# USB.net
KiCad netlist of a schematic drawn in Altium Designer
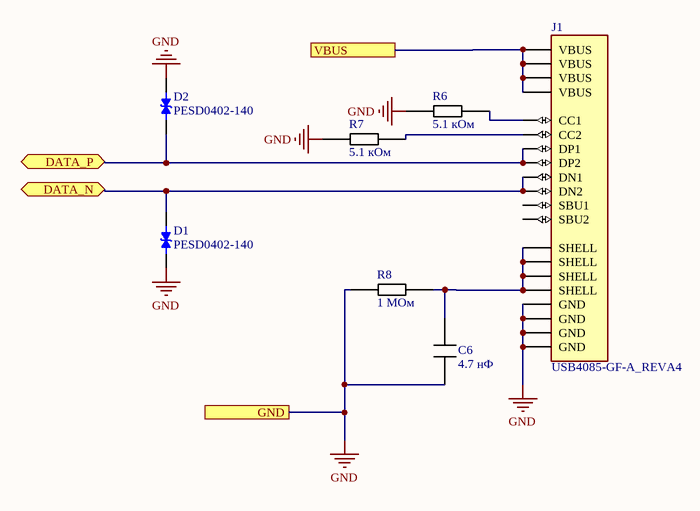
[diagram p0: USB.SchDoc]

(export (version "E")
  (design (tool "Eeschema 10.0.6"))
  (components
    (comp (ref "C6")
      (value "4.7 нФ")
      (footprint "WURTH 885012206012")
      (libsource (lib "Schlib1") (part "WURTH 885012206012"))
    )
    (comp (ref "D1")
      (value "PESD0402-140")
      (footprint "DIO_PESD0402-140")
      (description "40V Clamp - Ipp Tvs Diode Surface Mount 0402")
      (fields (field (name "MF") "Littelfuse Inc."))
      (libsource (lib "PESD0402-140") (part "PESD0402-140"))
    )
    (comp (ref "D2")
      (value "PESD0402-140")
      (footprint "DIO_PESD0402-140")
      (description "40V Clamp - Ipp Tvs Diode Surface Mount 0402")
      (fields (field (name "MF") "Littelfuse Inc."))
      (libsource (lib "PESD0402-140") (part "PESD0402-140"))
    )
    (comp (ref "J1")
      (value "USB4085-GF-A_REVA4")
      (footprint "GCT_USB4085-GF-A_REVA4")
      (fields (field (name "MP") "USB4085-GF-A") (field (name "MF") "Global Connector Technology"))
      (libsource (lib "USB4085-GF-A_REVA4") (part "USB4085-GF-A_REVA4"))
    )
    (comp (ref "R6")
      (value "5.1 кОм")
      (footprint "RC0805FR-075K1L")
      (libsource (lib "Schlib1") (part "RC0805FR-075K1L"))
    )
    (comp (ref "R7")
      (value "5.1 кОм")
      (footprint "RC0805FR-075K1L")
      (libsource (lib "Schlib1") (part "RC0805FR-075K1L"))
    )
    (comp (ref "R8")
      (value "1 МОм")
      (footprint "RC0805FR-071ML")
      (libsource (lib "Schlib1") (part "RC0805FR-071ML"))
    )
  )
  (nets
    (net (code "1") (name "/DATA_N") (class "Default")
      (node (ref "D1") (pin "1") (pinfunction "1_1") (pintype "passive"))
      (node (ref "J1") (pin "A7") (pinfunction "DN1_A7") (pintype "bidirectional"))
      (node (ref "J1") (pin "B7") (pinfunction "DN2_B7") (pintype "bidirectional"))
    )
    (net (code "2") (name "/DATA_P") (class "Default")
      (node (ref "D2") (pin "1") (pinfunction "1_1") (pintype "passive"))
      (node (ref "J1") (pin "A6") (pinfunction "DP1_A6") (pintype "bidirectional"))
      (node (ref "J1") (pin "B6") (pinfunction "DP2_B6") (pintype "bidirectional"))
    )
    (net (code "3") (name "/VBUS") (class "Default")
      (node (ref "J1") (pin "A4") (pinfunction "VBUS_A4") (pintype "power_in"))
      (node (ref "J1") (pin "A9") (pinfunction "VBUS_A9") (pintype "power_in"))
      (node (ref "J1") (pin "B4") (pinfunction "VBUS_B4") (pintype "power_in"))
      (node (ref "J1") (pin "B9") (pinfunction "VBUS_B9") (pintype "power_in"))
    )
    (net (code "4") (name "GND") (class "Default")
      (node (ref "C6") (pin "1") (pinfunction "3_1") (pintype "passive"))
      (node (ref "D1") (pin "2") (pinfunction "2_2") (pintype "passive"))
      (node (ref "D2") (pin "2") (pinfunction "2_2") (pintype "passive"))
      (node (ref "J1") (pin "A1") (pinfunction "GND_A1") (pintype "power_in"))
      (node (ref "J1") (pin "A12") (pinfunction "GND_A12") (pintype "power_in"))
      (node (ref "J1") (pin "B1") (pinfunction "GND_B1") (pintype "power_in"))
      (node (ref "J1") (pin "B12") (pinfunction "GND_B12") (pintype "power_in"))
      (node (ref "R6") (pin "1") (pinfunction "3_1") (pintype "passive"))
      (node (ref "R7") (pin "2") (pinfunction "2_2") (pintype "passive"))
      (node (ref "R8") (pin "1") (pinfunction "3_1") (pintype "passive"))
    )
    (net (code "5") (name "Net-(C6-Pad2)") (class "Default")
      (node (ref "C6") (pin "2") (pinfunction "2_2") (pintype "passive"))
      (node (ref "J1") (pin "S1") (pinfunction "SHELL_S1") (pintype "passive"))
      (node (ref "J1") (pin "S2") (pinfunction "SHELL_S2") (pintype "passive"))
      (node (ref "J1") (pin "S3") (pinfunction "SHELL_S3") (pintype "passive"))
      (node (ref "J1") (pin "S4") (pinfunction "SHELL_S4") (pintype "passive"))
      (node (ref "R8") (pin "2") (pinfunction "2_2") (pintype "passive"))
    )
    (net (code "6") (name "Net-(J1-CC1)") (class "Default")
      (node (ref "J1") (pin "A5") (pinfunction "CC1_A5") (pintype "bidirectional"))
      (node (ref "R6") (pin "2") (pinfunction "2_2") (pintype "passive"))
    )
    (net (code "7") (name "Net-(J1-CC2)") (class "Default")
      (node (ref "J1") (pin "B5") (pinfunction "CC2_B5") (pintype "bidirectional"))
      (node (ref "R7") (pin "1") (pinfunction "3_1") (pintype "passive"))
    )
    (net (code "8") (name "unconnected-(J1-SBU1-PadA8)") (class "Default")
      (node (ref "J1") (pin "A8") (pinfunction "SBU1_A8") (pintype "bidirectional"))
    )
    (net (code "9") (name "unconnected-(J1-SBU2-PadB8)") (class "Default")
      (node (ref "J1") (pin "B8") (pinfunction "SBU2_B8") (pintype "bidirectional"))
    )
  )
)
